# Polarshield_v1_5.net
KiCad netlist of a schematic drawn in EAGLE
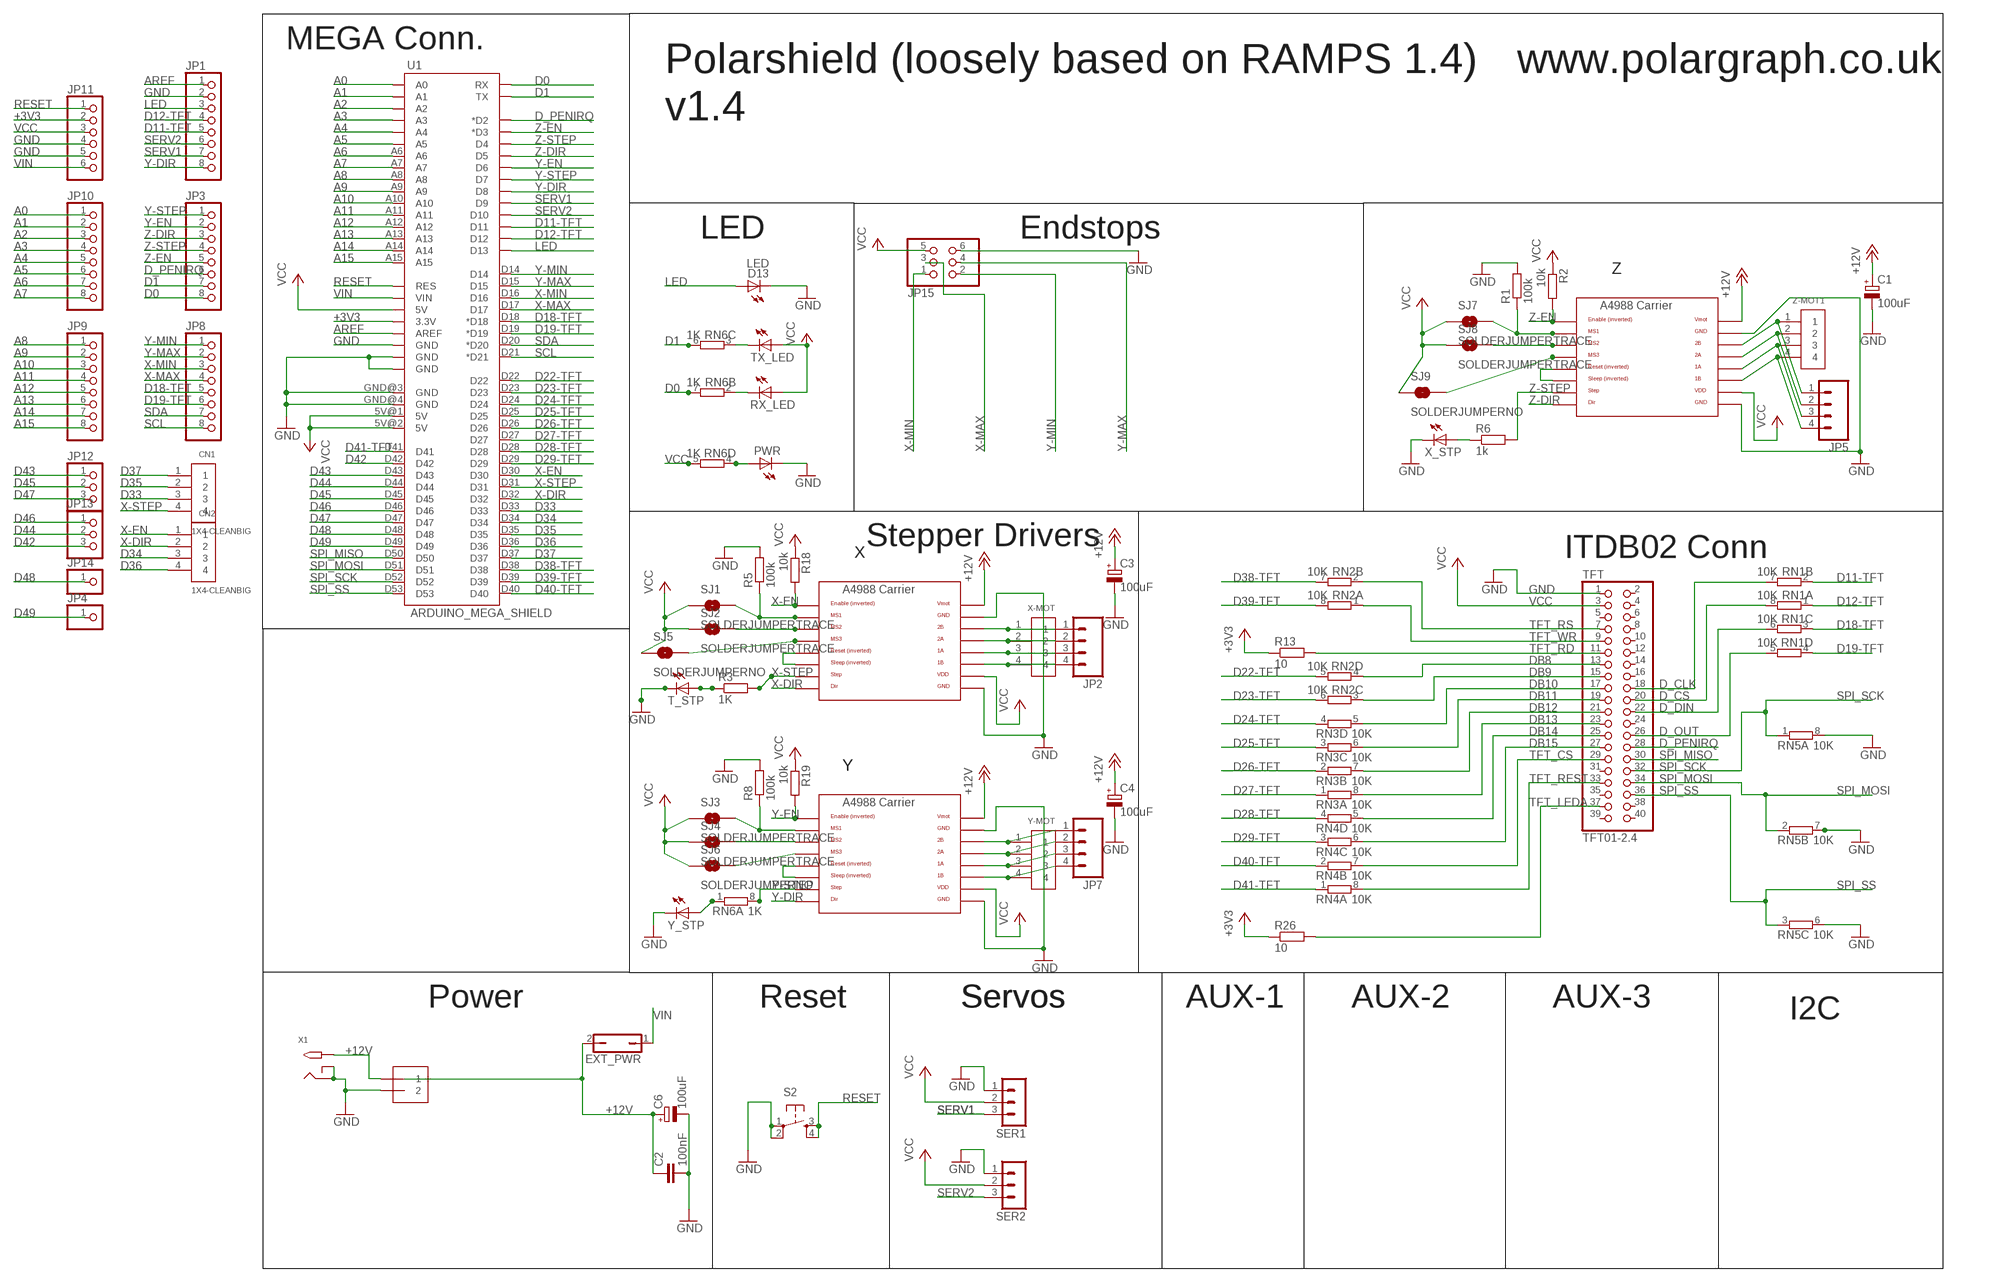
[diagram p0: schematic, sheet 1]

(export (version "E")
  (design (tool "Eeschema 10.0.6"))
  (components
    (comp (ref "C1")
      (value "100uF")
      (footprint "eagle-import:153CLV-0605")
      (libsource (lib "eagle-import") (part "CPOL-EU153CLV-0605"))
    )
    (comp (ref "C2")
      (value "100nF")
      (footprint "eagle-import:C0805")
      (libsource (lib "eagle-import") (part "C-EUC0805"))
    )
    (comp (ref "C3")
      (value "100uF")
      (footprint "eagle-import:153CLV-0605")
      (libsource (lib "eagle-import") (part "CPOL-EU153CLV-0605"))
    )
    (comp (ref "C4")
      (value "100uF")
      (footprint "eagle-import:153CLV-0605")
      (libsource (lib "eagle-import") (part "CPOL-EU153CLV-0605"))
    )
    (comp (ref "C6")
      (value "100uF")
      (footprint "eagle-import:153CLV-0605")
      (libsource (lib "eagle-import") (part "CPOL-EU153CLV-0605"))
    )
    (comp (ref "CN1")
      (value "1X4-CLEANBIG")
      (footprint "eagle-import:1X04-CLEANBIG")
      (libsource (lib "eagle-import") (part "1X4-CLEANBIG"))
    )
    (comp (ref "CN2")
      (value "1X4-CLEANBIG")
      (footprint "eagle-import:1X04-CLEANBIG")
      (libsource (lib "eagle-import") (part "1X4-CLEANBIG"))
    )
    (comp (ref "D13")
      (value "LED")
      (footprint "eagle-import:CHIP-LED0805")
      (libsource (lib "eagle-import") (part "LEDCHIP-LED0805"))
    )
    (comp (ref "EXT_PWR")
      (value "JP1Q")
      (footprint "eagle-import:JP1")
      (libsource (lib "eagle-import") (part "JP1Q"))
    )
    (comp (ref "J1")
      (value "1X2-3.5MM")
      (footprint "eagle-import:1X2-3.5MM")
      (libsource (lib "eagle-import") (part "1X2-3.5MM"))
    )
    (comp (ref "JP1")
      (value "PINHD-1X8CLEANBIG")
      (footprint "eagle-import:1X08-CLEANBIG")
      (libsource (lib "eagle-import") (part "PINHD-1X8CLEANBIG"))
    )
    (comp (ref "JP2")
      (value "M04SCREW")
      (footprint "eagle-import:SCREWTERMINAL-3.5MM-4")
      (libsource (lib "eagle-import") (part "M04SCREW"))
    )
    (comp (ref "JP3")
      (value "PINHD-1X8CLEANBIG")
      (footprint "eagle-import:1X08-CLEANBIG")
      (libsource (lib "eagle-import") (part "PINHD-1X8CLEANBIG"))
    )
    (comp (ref "JP4")
      (value "PINHD-1X1CB")
      (footprint "eagle-import:1X01-CLEANBIG")
      (libsource (lib "eagle-import") (part "PINHD-1X1CB"))
    )
    (comp (ref "JP5")
      (value "M04SCREW")
      (footprint "eagle-import:SCREWTERMINAL-3.5MM-4")
      (libsource (lib "eagle-import") (part "M04SCREW"))
    )
    (comp (ref "JP7")
      (value "M04SCREW")
      (footprint "eagle-import:SCREWTERMINAL-3.5MM-4")
      (libsource (lib "eagle-import") (part "M04SCREW"))
    )
    (comp (ref "JP8")
      (value "PINHD-1X8CLEANBIG")
      (footprint "eagle-import:1X08-CLEANBIG")
      (libsource (lib "eagle-import") (part "PINHD-1X8CLEANBIG"))
    )
    (comp (ref "JP9")
      (value "PINHD-1X8CLEANBIG")
      (footprint "eagle-import:1X08-CLEANBIG")
      (libsource (lib "eagle-import") (part "PINHD-1X8CLEANBIG"))
    )
    (comp (ref "JP10")
      (value "PINHD-1X8CLEANBIG")
      (footprint "eagle-import:1X08-CLEANBIG")
      (libsource (lib "eagle-import") (part "PINHD-1X8CLEANBIG"))
    )
    (comp (ref "JP11")
      (value "PINHD-1X6CB")
      (footprint "eagle-import:1X06-CLEANBIG")
      (libsource (lib "eagle-import") (part "PINHD-1X6CB"))
    )
    (comp (ref "JP12")
      (value "PINHD-1X3CB")
      (footprint "eagle-import:1X03-CLEANBIG")
      (libsource (lib "eagle-import") (part "PINHD-1X3CB"))
    )
    (comp (ref "JP13")
      (value "PINHD-1X3CB")
      (footprint "eagle-import:1X03-CLEANBIG")
      (libsource (lib "eagle-import") (part "PINHD-1X3CB"))
    )
    (comp (ref "JP14")
      (value "PINHD-1X1CB")
      (footprint "eagle-import:1X01-CLEANBIG")
      (libsource (lib "eagle-import") (part "PINHD-1X1CB"))
    )
    (comp (ref "JP15")
      (value "PINHD-2X3")
      (footprint "eagle-import:2X03")
      (libsource (lib "eagle-import") (part "PINHD-2X3"))
    )
    (comp (ref "PWR")
      (value "LEDCHIP-LED0805")
      (footprint "eagle-import:CHIP-LED0805")
      (libsource (lib "eagle-import") (part "LEDCHIP-LED0805"))
    )
    (comp (ref "R1")
      (value "100k")
      (footprint "eagle-import:R0805")
      (libsource (lib "eagle-import") (part "R-EU_R0805"))
    )
    (comp (ref "R2")
      (value "10k")
      (footprint "eagle-import:R0805")
      (libsource (lib "eagle-import") (part "R-EU_R0805"))
    )
    (comp (ref "R3")
      (value "1K")
      (footprint "eagle-import:R0805")
      (libsource (lib "eagle-import") (part "R-EU_R0805"))
    )
    (comp (ref "R5")
      (value "100k")
      (footprint "eagle-import:R0805")
      (libsource (lib "eagle-import") (part "R-EU_R0805"))
    )
    (comp (ref "R6")
      (value "1k")
      (footprint "eagle-import:R0805")
      (libsource (lib "eagle-import") (part "R-EU_R0805"))
    )
    (comp (ref "R8")
      (value "100k")
      (footprint "eagle-import:R0805")
      (libsource (lib "eagle-import") (part "R-EU_R0805"))
    )
    (comp (ref "R13")
      (value "10")
      (footprint "eagle-import:R0805")
      (libsource (lib "eagle-import") (part "resistor_R-EU_R0805"))
    )
    (comp (ref "R18")
      (value "10k")
      (footprint "eagle-import:R0805")
      (libsource (lib "eagle-import") (part "R-EU_R0805"))
    )
    (comp (ref "R19")
      (value "10k")
      (footprint "eagle-import:R0805")
      (libsource (lib "eagle-import") (part "R-EU_R0805"))
    )
    (comp (ref "R26")
      (value "10")
      (footprint "eagle-import:R0805")
      (libsource (lib "eagle-import") (part "resistor_R-EU_R0805"))
    )
    (comp (ref "RN1")
      (value "10K")
      (footprint "eagle-import:EXBS8V")
      (libsource (lib "eagle-import") (part "4R-NEXBS8V"))
    )
    (comp (ref "RN2")
      (value "10K")
      (footprint "eagle-import:EXBS8V")
      (libsource (lib "eagle-import") (part "4R-NEXBS8V"))
    )
    (comp (ref "RN3")
      (value "10K")
      (footprint "eagle-import:EXBS8V")
      (libsource (lib "eagle-import") (part "4R-NEXBS8V"))
    )
    (comp (ref "RN4")
      (value "10K")
      (footprint "eagle-import:EXBS8V")
      (libsource (lib "eagle-import") (part "4R-NEXBS8V"))
    )
    (comp (ref "RN5")
      (value "10K")
      (footprint "eagle-import:EXBS8V")
      (libsource (lib "eagle-import") (part "4R-NEXBS8V"))
    )
    (comp (ref "RN6")
      (value "1K")
      (footprint "eagle-import:EXBS8V")
      (libsource (lib "eagle-import") (part "4R-NEXBS8V"))
    )
    (comp (ref "RX_LED")
      (value "LEDCHIP-LED0805")
      (footprint "eagle-import:CHIP-LED0805")
      (libsource (lib "eagle-import") (part "LEDCHIP-LED0805"))
    )
    (comp (ref "S2")
      (value "TAC_SWITCHPTH")
      (footprint "eagle-import:TACTILE-PTH")
      (libsource (lib "eagle-import") (part "TAC_SWITCHPTH"))
    )
    (comp (ref "SER1")
      (value "3PIN-HEADER")
      (footprint "eagle-import:3PIN-HEADER")
      (libsource (lib "eagle-import") (part "3PIN-HEADER"))
    )
    (comp (ref "SER2")
      (value "3PIN-HEADER")
      (footprint "eagle-import:3PIN-HEADER")
      (libsource (lib "eagle-import") (part "3PIN-HEADER"))
    )
    (comp (ref "SJ1")
      (value "SOLDERJUMPERTRACE")
      (footprint "eagle-import:SJ_2S-TRACE")
      (libsource (lib "eagle-import") (part "SOLDERJUMPERTRACE"))
    )
    (comp (ref "SJ2")
      (value "SOLDERJUMPERTRACE")
      (footprint "eagle-import:SJ_2S-TRACE")
      (libsource (lib "eagle-import") (part "SOLDERJUMPERTRACE"))
    )
    (comp (ref "SJ3")
      (value "SOLDERJUMPERTRACE")
      (footprint "eagle-import:SJ_2S-TRACE")
      (libsource (lib "eagle-import") (part "SOLDERJUMPERTRACE"))
    )
    (comp (ref "SJ4")
      (value "SOLDERJUMPERTRACE")
      (footprint "eagle-import:SJ_2S-TRACE")
      (libsource (lib "eagle-import") (part "SOLDERJUMPERTRACE"))
    )
    (comp (ref "SJ5")
      (value "SOLDERJUMPERNO")
      (footprint "eagle-import:SJ_2S-NO")
      (libsource (lib "eagle-import") (part "SOLDERJUMPERNO"))
    )
    (comp (ref "SJ6")
      (value "SOLDERJUMPERNO")
      (footprint "eagle-import:SJ_2S-NO")
      (libsource (lib "eagle-import") (part "SOLDERJUMPERNO"))
    )
    (comp (ref "SJ7")
      (value "SOLDERJUMPERTRACE")
      (footprint "eagle-import:SJ_2S-TRACE")
      (libsource (lib "eagle-import") (part "SOLDERJUMPERTRACE"))
    )
    (comp (ref "SJ8")
      (value "SOLDERJUMPERTRACE")
      (footprint "eagle-import:SJ_2S-TRACE")
      (libsource (lib "eagle-import") (part "SOLDERJUMPERTRACE"))
    )
    (comp (ref "SJ9")
      (value "SOLDERJUMPERNO")
      (footprint "eagle-import:SJ_2S-NO")
      (libsource (lib "eagle-import") (part "SOLDERJUMPERNO"))
    )
    (comp (ref "TFT")
      (value "TFT01-2.4")
      (footprint "eagle-import:TFT01-2.4")
      (libsource (lib "eagle-import") (part "TFT01-2.4"))
    )
    (comp (ref "TX_LED")
      (value "LEDCHIP-LED0805")
      (footprint "eagle-import:CHIP-LED0805")
      (libsource (lib "eagle-import") (part "LEDCHIP-LED0805"))
    )
    (comp (ref "T_STP")
      (value "LEDCHIP-LED0805")
      (footprint "eagle-import:CHIP-LED0805")
      (libsource (lib "eagle-import") (part "LEDCHIP-LED0805"))
    )
    (comp (ref "U$1")
      (value "A4988BREAKOUT")
      (footprint "eagle-import:A4988BREAKOUT")
      (libsource (lib "eagle-import") (part "A4988BREAKOUT"))
    )
    (comp (ref "U$6")
      (value "A4988BREAKOUT")
      (footprint "eagle-import:A4988BREAKOUT")
      (libsource (lib "eagle-import") (part "A4988BREAKOUT"))
    )
    (comp (ref "U$7")
      (value "A4988BREAKOUT")
      (footprint "eagle-import:A4988BREAKOUT")
      (libsource (lib "eagle-import") (part "A4988BREAKOUT"))
    )
    (comp (ref "U1")
      (value "ARDUINO_MEGA_SHIELD")
      (footprint "eagle-import:ARDUINO_MEGA_SHIELD")
      (libsource (lib "eagle-import") (part "ARDUINO_MEGA_SHIELD"))
    )
    (comp (ref "X-MOT")
      (value "1X4-BIG")
      (footprint "eagle-import:1X04-BIG")
      (libsource (lib "eagle-import") (part "1X4-BIG"))
    )
    (comp (ref "X1")
      (value "2.1MMJACKTHM")
      (footprint "eagle-import:PJ-102A")
      (libsource (lib "eagle-import") (part "2.1MMJACKTHM"))
    )
    (comp (ref "X_STP")
      (value "LEDCHIP-LED0805")
      (footprint "eagle-import:CHIP-LED0805")
      (libsource (lib "eagle-import") (part "LEDCHIP-LED0805"))
    )
    (comp (ref "Y-MOT")
      (value "1X4-BIG")
      (footprint "eagle-import:1X04-BIG")
      (libsource (lib "eagle-import") (part "1X4-BIG"))
    )
    (comp (ref "Y_STP")
      (value "LEDCHIP-LED0805")
      (footprint "eagle-import:CHIP-LED0805")
      (libsource (lib "eagle-import") (part "LEDCHIP-LED0805"))
    )
    (comp (ref "Z-MOT1")
      (value "1X4-BIG")
      (footprint "eagle-import:1X04-BIG")
      (libsource (lib "eagle-import") (part "1X4-BIG"))
    )
  )
  (nets
    (net (code "1") (name "+3V3") (class "Default")
      (node (ref "JP11") (pin "2") (pinfunction "2_2") (pintype "passive"))
      (node (ref "R13") (pin "1") (pinfunction "1_1") (pintype "passive"))
      (node (ref "R26") (pin "1") (pinfunction "1_1") (pintype "passive"))
      (node (ref "U1") (pin "3.3V") (pinfunction "3.3V_3.3V") (pintype "bidirectional"))
    )
    (net (code "2") (name "+12V") (class "Default")
      (node (ref "C1") (pin "+") (pinfunction "+_+") (pintype "passive"))
      (node (ref "C2") (pin "1") (pinfunction "1_1") (pintype "passive"))
      (node (ref "C3") (pin "+") (pinfunction "+_+") (pintype "passive"))
      (node (ref "C4") (pin "+") (pinfunction "+_+") (pintype "passive"))
      (node (ref "C6") (pin "+") (pinfunction "+_+") (pintype "passive"))
      (node (ref "EXT_PWR") (pin "2") (pinfunction "2_2") (pintype "passive"))
      (node (ref "J1") (pin "1") (pinfunction "1_1") (pintype "passive"))
      (node (ref "U$1") (pin "VMOT") (pinfunction "VMOT_VMOT") (pintype "power_in"))
      (node (ref "U$6") (pin "VMOT") (pinfunction "VMOT_VMOT") (pintype "power_in"))
      (node (ref "U$7") (pin "VMOT") (pinfunction "VMOT_VMOT") (pintype "power_in"))
      (node (ref "X1") (pin "TIP") (pinfunction "TIP_TIP") (pintype "bidirectional"))
    )
    (net (code "3") (name "/A0") (class "Default")
      (node (ref "JP10") (pin "1") (pinfunction "1_1") (pintype "passive"))
      (node (ref "U1") (pin "A0") (pinfunction "A0_A0") (pintype "bidirectional"))
    )
    (net (code "4") (name "/A1") (class "Default")
      (node (ref "JP10") (pin "2") (pinfunction "2_2") (pintype "passive"))
      (node (ref "U1") (pin "A1") (pinfunction "A1_A1") (pintype "bidirectional"))
    )
    (net (code "5") (name "/A2") (class "Default")
      (node (ref "JP10") (pin "3") (pinfunction "3_3") (pintype "passive"))
      (node (ref "U1") (pin "A2") (pinfunction "A2_A2") (pintype "bidirectional"))
    )
    (net (code "6") (name "/A3") (class "Default")
      (node (ref "JP10") (pin "4") (pinfunction "4_4") (pintype "passive"))
      (node (ref "U1") (pin "A3") (pinfunction "A3_A3") (pintype "bidirectional"))
    )
    (net (code "7") (name "/A4") (class "Default")
      (node (ref "JP10") (pin "5") (pinfunction "5_5") (pintype "passive"))
      (node (ref "U1") (pin "A4") (pinfunction "A4_A4") (pintype "bidirectional"))
    )
    (net (code "8") (name "/A5") (class "Default")
      (node (ref "JP10") (pin "6") (pinfunction "6_6") (pintype "passive"))
      (node (ref "U1") (pin "A5") (pinfunction "A5_A5") (pintype "bidirectional"))
    )
    (net (code "9") (name "/A6") (class "Default")
      (node (ref "JP10") (pin "7") (pinfunction "7_7") (pintype "passive"))
      (node (ref "U1") (pin "A6") (pinfunction "A6_A6") (pintype "bidirectional"))
    )
    (net (code "10") (name "/A7") (class "Default")
      (node (ref "JP10") (pin "8") (pinfunction "8_8") (pintype "passive"))
      (node (ref "U1") (pin "A7") (pinfunction "A7_A7") (pintype "bidirectional"))
    )
    (net (code "11") (name "/A8") (class "Default")
      (node (ref "JP9") (pin "1") (pinfunction "1_1") (pintype "passive"))
      (node (ref "U1") (pin "A8") (pinfunction "A8_A8") (pintype "bidirectional"))
    )
    (net (code "12") (name "/A9") (class "Default")
      (node (ref "JP9") (pin "2") (pinfunction "2_2") (pintype "passive"))
      (node (ref "U1") (pin "A9") (pinfunction "A9_A9") (pintype "bidirectional"))
    )
    (net (code "13") (name "/A10") (class "Default")
      (node (ref "JP9") (pin "3") (pinfunction "3_3") (pintype "passive"))
      (node (ref "U1") (pin "A10") (pinfunction "A10_A10") (pintype "bidirectional"))
    )
    (net (code "14") (name "/A11") (class "Default")
      (node (ref "JP9") (pin "4") (pinfunction "4_4") (pintype "passive"))
      (node (ref "U1") (pin "A11") (pinfunction "A11_A11") (pintype "bidirectional"))
    )
    (net (code "15") (name "/A12") (class "Default")
      (node (ref "JP9") (pin "5") (pinfunction "5_5") (pintype "passive"))
      (node (ref "U1") (pin "A12") (pinfunction "A12_A12") (pintype "bidirectional"))
    )
    (net (code "16") (name "/A13") (class "Default")
      (node (ref "JP9") (pin "6") (pinfunction "6_6") (pintype "passive"))
      (node (ref "U1") (pin "A13") (pinfunction "A13_A13") (pintype "bidirectional"))
    )
    (net (code "17") (name "/A14") (class "Default")
      (node (ref "JP9") (pin "7") (pinfunction "7_7") (pintype "passive"))
      (node (ref "U1") (pin "A14") (pinfunction "A14_A14") (pintype "bidirectional"))
    )
    (net (code "18") (name "/A15") (class "Default")
      (node (ref "JP9") (pin "8") (pinfunction "8_8") (pintype "passive"))
      (node (ref "U1") (pin "A15") (pinfunction "A15_A15") (pintype "bidirectional"))
    )
    (net (code "19") (name "/AREF") (class "Default")
      (node (ref "JP1") (pin "1") (pinfunction "1_1") (pintype "passive"))
      (node (ref "U1") (pin "AREF") (pinfunction "AREF_AREF") (pintype "bidirectional"))
    )
    (net (code "20") (name "/D0") (class "Default")
      (node (ref "JP3") (pin "8") (pinfunction "8_8") (pintype "passive"))
      (node (ref "RN6") (pin "7") (pinfunction "2_7") (pintype "passive"))
      (node (ref "U1") (pin "RX") (pinfunction "RX_RX") (pintype "bidirectional"))
    )
    (net (code "21") (name "/D1") (class "Default")
      (node (ref "JP3") (pin "7") (pinfunction "7_7") (pintype "passive"))
      (node (ref "RN6") (pin "6") (pinfunction "2_6") (pintype "passive"))
      (node (ref "U1") (pin "TX") (pinfunction "TX_TX") (pintype "bidirectional"))
    )
    (net (code "22") (name "/D11-TFT") (class "Default")
      (node (ref "JP1") (pin "5") (pinfunction "5_5") (pintype "passive"))
      (node (ref "RN1") (pin "2") (pinfunction "1_2") (pintype "passive"))
      (node (ref "U1") (pin "D11") (pinfunction "D11_D11") (pintype "bidirectional"))
    )
    (net (code "23") (name "/D12-TFT") (class "Default")
      (node (ref "JP1") (pin "4") (pinfunction "4_4") (pintype "passive"))
      (node (ref "RN1") (pin "1") (pinfunction "1_1") (pintype "passive"))
      (node (ref "U1") (pin "D12") (pinfunction "D12_D12") (pintype "bidirectional"))
    )
    (net (code "24") (name "/D18-TFT") (class "Default")
      (node (ref "JP8") (pin "5") (pinfunction "5_5") (pintype "passive"))
      (node (ref "RN1") (pin "3") (pinfunction "1_3") (pintype "passive"))
      (node (ref "U1") (pin "D18") (pinfunction "*D18_D18") (pintype "bidirectional"))
    )
    (net (code "25") (name "/D19-TFT") (class "Default")
      (node (ref "JP8") (pin "6") (pinfunction "6_6") (pintype "passive"))
      (node (ref "RN1") (pin "4") (pinfunction "1_4") (pintype "passive"))
      (node (ref "U1") (pin "D19") (pinfunction "*D19_D19") (pintype "bidirectional"))
    )
    (net (code "26") (name "/D22-TFT") (class "Default")
      (node (ref "RN2") (pin "5") (pinfunction "2_5") (pintype "passive"))
      (node (ref "U1") (pin "D22") (pinfunction "D22_D22") (pintype "bidirectional"))
    )
    (net (code "27") (name "/D23-TFT") (class "Default")
      (node (ref "RN2") (pin "6") (pinfunction "2_6") (pintype "passive"))
      (node (ref "U1") (pin "D23") (pinfunction "D23_D23") (pintype "bidirectional"))
    )
    (net (code "28") (name "/D24-TFT") (class "Default")
      (node (ref "RN3") (pin "4") (pinfunction "1_4") (pintype "passive"))
      (node (ref "U1") (pin "D24") (pinfunction "D24_D24") (pintype "bidirectional"))
    )
    (net (code "29") (name "/D25-TFT") (class "Default")
      (node (ref "RN3") (pin "3") (pinfunction "1_3") (pintype "passive"))
      (node (ref "U1") (pin "D25") (pinfunction "D25_D25") (pintype "bidirectional"))
    )
    (net (code "30") (name "/D26-TFT") (class "Default")
      (node (ref "RN3") (pin "2") (pinfunction "1_2") (pintype "passive"))
      (node (ref "U1") (pin "D26") (pinfunction "D26_D26") (pintype "bidirectional"))
    )
    (net (code "31") (name "/D27-TFT") (class "Default")
      (node (ref "RN3") (pin "1") (pinfunction "1_1") (pintype "passive"))
      (node (ref "U1") (pin "D27") (pinfunction "D27_D27") (pintype "bidirectional"))
    )
    (net (code "32") (name "/D28-TFT") (class "Default")
      (node (ref "RN4") (pin "4") (pinfunction "1_4") (pintype "passive"))
      (node (ref "U1") (pin "D28") (pinfunction "D28_D28") (pintype "bidirectional"))
    )
    (net (code "33") (name "/D29-TFT") (class "Default")
      (node (ref "RN4") (pin "3") (pinfunction "1_3") (pintype "passive"))
      (node (ref "U1") (pin "D29") (pinfunction "D29_D29") (pintype "bidirectional"))
    )
    (net (code "34") (name "/D33") (class "Default")
      (node (ref "CN1") (pin "3") (pinfunction "3_3") (pintype "bidirectional"))
      (node (ref "U1") (pin "D33") (pinfunction "D33_D33") (pintype "bidirectional"))
    )
    (net (code "35") (name "/D34") (class "Default")
      (node (ref "CN2") (pin "3") (pinfunction "3_3") (pintype "bidirectional"))
      (node (ref "U1") (pin "D34") (pinfunction "D34_D34") (pintype "bidirectional"))
    )
    (net (code "36") (name "/D35") (class "Default")
      (node (ref "CN1") (pin "2") (pinfunction "2_2") (pintype "bidirectional"))
      (node (ref "U1") (pin "D35") (pinfunction "D35_D35") (pintype "bidirectional"))
    )
    (net (code "37") (name "/D36") (class "Default")
      (node (ref "CN2") (pin "4") (pinfunction "4_4") (pintype "bidirectional"))
      (node (ref "U1") (pin "D36") (pinfunction "D36_D36") (pintype "bidirectional"))
    )
    (net (code "38") (name "/D37") (class "Default")
      (node (ref "CN1") (pin "1") (pinfunction "1_1") (pintype "bidirectional"))
      (node (ref "U1") (pin "D37") (pinfunction "D37_D37") (pintype "bidirectional"))
    )
    (net (code "39") (name "/D38-TFT") (class "Default")
      (node (ref "RN2") (pin "7") (pinfunction "2_7") (pintype "passive"))
      (node (ref "U1") (pin "D38") (pinfunction "D38_D38") (pintype "bidirectional"))
    )
    (net (code "40") (name "/D39-TFT") (class "Default")
      (node (ref "RN2") (pin "8") (pinfunction "2_8") (pintype "passive"))
      (node (ref "U1") (pin "D39") (pinfunction "D39_D39") (pintype "bidirectional"))
    )
    (net (code "41") (name "/D40-TFT") (class "Default")
      (node (ref "RN4") (pin "2") (pinfunction "1_2") (pintype "passive"))
      (node (ref "U1") (pin "D40") (pinfunction "D40_D40") (pintype "bidirectional"))
    )
    (net (code "42") (name "/D41-TFT") (class "Default")
      (node (ref "RN4") (pin "1") (pinfunction "1_1") (pintype "passive"))
      (node (ref "U1") (pin "D41") (pinfunction "D41_D41") (pintype "bidirectional"))
    )
    (net (code "43") (name "/D42") (class "Default")
      (node (ref "JP13") (pin "3") (pinfunction "3_3") (pintype "passive"))
      (node (ref "U1") (pin "D42") (pinfunction "D42_D42") (pintype "bidirectional"))
    )
    (net (code "44") (name "/D43") (class "Default")
      (node (ref "JP12") (pin "1") (pinfunction "1_1") (pintype "passive"))
      (node (ref "U1") (pin "D43") (pinfunction "D43_D43") (pintype "bidirectional"))
    )
    (net (code "45") (name "/D44") (class "Default")
      (node (ref "JP13") (pin "2") (pinfunction "2_2") (pintype "passive"))
      (node (ref "U1") (pin "D44") (pinfunction "D44_D44") (pintype "bidirectional"))
    )
    (net (code "46") (name "/D45") (class "Default")
      (node (ref "JP12") (pin "2") (pinfunction "2_2") (pintype "passive"))
      (node (ref "U1") (pin "D45") (pinfunction "D45_D45") (pintype "bidirectional"))
    )
    (net (code "47") (name "/D46") (class "Default")
      (node (ref "JP13") (pin "1") (pinfunction "1_1") (pintype "passive"))
      (node (ref "U1") (pin "D46") (pinfunction "D46_D46") (pintype "bidirectional"))
    )
    (net (code "48") (name "/D47") (class "Default")
      (node (ref "JP12") (pin "3") (pinfunction "3_3") (pintype "passive"))
      (node (ref "U1") (pin "D47") (pinfunction "D47_D47") (pintype "bidirectional"))
    )
    (net (code "49") (name "/D48") (class "Default")
      (node (ref "JP14") (pin "1") (pinfunction "1_1") (pintype "passive"))
      (node (ref "U1") (pin "D48") (pinfunction "D48_D48") (pintype "bidirectional"))
    )
    (net (code "50") (name "/D49") (class "Default")
      (node (ref "JP4") (pin "1") (pinfunction "1_1") (pintype "passive"))
      (node (ref "U1") (pin "D49") (pinfunction "D49_D49") (pintype "bidirectional"))
    )
    (net (code "51") (name "/DB8") (class "Default")
      (node (ref "RN2") (pin "4") (pinfunction "1_4") (pintype "passive"))
      (node (ref "TFT") (pin "13") (pinfunction "13_13") (pintype "passive"))
    )
    (net (code "52") (name "/DB9") (class "Default")
      (node (ref "RN2") (pin "3") (pinfunction "1_3") (pintype "passive"))
      (node (ref "TFT") (pin "15") (pinfunction "15_15") (pintype "passive"))
    )
    (net (code "53") (name "/DB10") (class "Default")
      (node (ref "RN3") (pin "5") (pinfunction "2_5") (pintype "passive"))
      (node (ref "TFT") (pin "17") (pinfunction "17_17") (pintype "passive"))
    )
    (net (code "54") (name "/DB11") (class "Default")
      (node (ref "RN3") (pin "6") (pinfunction "2_6") (pintype "passive"))
      (node (ref "TFT") (pin "19") (pinfunction "19_19") (pintype "passive"))
    )
    (net (code "55") (name "/DB12") (class "Default")
      (node (ref "RN3") (pin "7") (pinfunction "2_7") (pintype "passive"))
      (node (ref "TFT") (pin "21") (pinfunction "21_21") (pintype "passive"))
    )
    (net (code "56") (name "/DB13") (class "Default")
      (node (ref "RN3") (pin "8") (pinfunction "2_8") (pintype "passive"))
      (node (ref "TFT") (pin "23") (pinfunction "23_23") (pintype "passive"))
    )
    (net (code "57") (name "/DB14") (class "Default")
      (node (ref "RN4") (pin "5") (pinfunction "2_5") (pintype "passive"))
      (node (ref "TFT") (pin "25") (pinfunction "25_25") (pintype "passive"))
    )
    (net (code "58") (name "/DB15") (class "Default")
      (node (ref "RN4") (pin "6") (pinfunction "2_6") (pintype "passive"))
      (node (ref "TFT") (pin "27") (pinfunction "27_27") (pintype "passive"))
    )
    (net (code "59") (name "/D_CLK") (class "Default")
      (node (ref "RN1") (pin "7") (pinfunction "2_7") (pintype "passive"))
      (node (ref "TFT") (pin "18") (pinfunction "18_18") (pintype "passive"))
    )
    (net (code "60") (name "/D_CS") (class "Default")
      (node (ref "RN1") (pin "8") (pinfunction "2_8") (pintype "passive"))
      (node (ref "TFT") (pin "20") (pinfunction "20_20") (pintype "passive"))
    )
    (net (code "61") (name "/D_DIN") (class "Default")
      (node (ref "RN1") (pin "6") (pinfunction "2_6") (pintype "passive"))
      (node (ref "TFT") (pin "22") (pinfunction "22_22") (pintype "passive"))
    )
    (net (code "62") (name "/D_OUT") (class "Default")
      (node (ref "RN1") (pin "5") (pinfunction "2_5") (pintype "passive"))
      (node (ref "TFT") (pin "26") (pinfunction "26_26") (pintype "passive"))
    )
    (net (code "63") (name "/D_PENIRQ") (class "Default")
      (node (ref "JP3") (pin "6") (pinfunction "6_6") (pintype "passive"))
      (node (ref "TFT") (pin "28") (pinfunction "28_28") (pintype "passive"))
      (node (ref "U1") (pin "D2") (pinfunction "*D2_D2") (pintype "bidirectional"))
    )
    (net (code "64") (name "/LED") (class "Default")
      (node (ref "D13") (pin "A") (pinfunction "A_A") (pintype "passive"))
      (node (ref "JP1") (pin "3") (pinfunction "3_3") (pintype "passive"))
      (node (ref "U1") (pin "D13") (pinfunction "D13_D13") (pintype "bidirectional"))
    )
    (net (code "65") (name "/RESET") (class "Default")
      (node (ref "JP11") (pin "1") (pinfunction "1_1") (pintype "passive"))
      (node (ref "S2") (pin "3") (pinfunction "3_3") (pintype "passive"))
      (node (ref "S2") (pin "4") (pinfunction "4_4") (pintype "passive"))
      (node (ref "U1") (pin "RES") (pinfunction "RES_RES") (pintype "bidirectional"))
    )
    (net (code "66") (name "/SCL") (class "Default")
      (node (ref "JP8") (pin "8") (pinfunction "8_8") (pintype "passive"))
      (node (ref "U1") (pin "D21") (pinfunction "*D21_D21") (pintype "bidirectional"))
    )
    (net (code "67") (name "/SDA") (class "Default")
      (node (ref "JP8") (pin "7") (pinfunction "7_7") (pintype "passive"))
      (node (ref "U1") (pin "D20") (pinfunction "*D20_D20") (pintype "bidirectional"))
    )
    (net (code "68") (name "/SERV1") (class "Default")
      (node (ref "JP1") (pin "7") (pinfunction "7_7") (pintype "passive"))
      (node (ref "SER1") (pin "3") (pinfunction "3_3") (pintype "passive"))
      (node (ref "U1") (pin "D9") (pinfunction "D9_D9") (pintype "bidirectional"))
    )
    (net (code "69") (name "/SERV2") (class "Default")
      (node (ref "JP1") (pin "6") (pinfunction "6_6") (pintype "passive"))
      (node (ref "SER2") (pin "3") (pinfunction "3_3") (pintype "passive"))
      (node (ref "U1") (pin "D10") (pinfunction "D10_D10") (pintype "bidirectional"))
    )
    (net (code "70") (name "/SPI_MISO") (class "Default")
      (node (ref "TFT") (pin "30") (pinfunction "30_30") (pintype "passive"))
      (node (ref "U1") (pin "D50") (pinfunction "D50_D50") (pintype "bidirectional"))
    )
    (net (code "71") (name "/SPI_MOSI") (class "Default")
      (node (ref "RN5") (pin "2") (pinfunction "1_2") (pintype "passive"))
      (node (ref "TFT") (pin "34") (pinfunction "34_34") (pintype "passive"))
      (node (ref "U1") (pin "D51") (pinfunction "D51_D51") (pintype "bidirectional"))
    )
    (net (code "72") (name "/SPI_SCK") (class "Default")
      (node (ref "RN5") (pin "1") (pinfunction "1_1") (pintype "passive"))
      (node (ref "TFT") (pin "32") (pinfunction "32_32") (pintype "passive"))
      (node (ref "U1") (pin "D52") (pinfunction "D52_D52") (pintype "bidirectional"))
    )
    (net (code "73") (name "/SPI_SS") (class "Default")
      (node (ref "RN5") (pin "3") (pinfunction "1_3") (pintype "passive"))
      (node (ref "TFT") (pin "36") (pinfunction "36_36") (pintype "passive"))
      (node (ref "U1") (pin "D53") (pinfunction "D53_D53") (pintype "bidirectional"))
    )
    (net (code "74") (name "/TFT_CS") (class "Default")
      (node (ref "RN4") (pin "7") (pinfunction "2_7") (pintype "passive"))
      (node (ref "TFT") (pin "29") (pinfunction "29_29") (pintype "passive"))
    )
    (net (code "75") (name "/TFT_LEDA") (class "Default")
      (node (ref "R26") (pin "2") (pinfunction "2_2") (pintype "passive"))
      (node (ref "TFT") (pin "37") (pinfunction "37_37") (pintype "passive"))
    )
    (net (code "76") (name "/TFT_RD") (class "Default")
      (node (ref "R13") (pin "2") (pinfunction "2_2") (pintype "passive"))
      (node (ref "TFT") (pin "11") (pinfunction "11_11") (pintype "passive"))
    )
    (net (code "77") (name "/TFT_REST") (class "Default")
      (node (ref "RN4") (pin "8") (pinfunction "2_8") (pintype "passive"))
      (node (ref "TFT") (pin "33") (pinfunction "33_33") (pintype "passive"))
    )
    (net (code "78") (name "/TFT_RS") (class "Default")
      (node (ref "RN2") (pin "2") (pinfunction "1_2") (pintype "passive"))
      (node (ref "TFT") (pin "7") (pinfunction "7_7") (pintype "passive"))
    )
    (net (code "79") (name "/TFT_WR") (class "Default")
      (node (ref "RN2") (pin "1") (pinfunction "1_1") (pintype "passive"))
      (node (ref "TFT") (pin "9") (pinfunction "9_9") (pintype "passive"))
    )
    (net (code "80") (name "/VIN") (class "Default")
      (node (ref "EXT_PWR") (pin "1") (pinfunction "1_1") (pintype "passive"))
      (node (ref "JP11") (pin "6") (pinfunction "6_6") (pintype "passive"))
      (node (ref "U1") (pin "VIN") (pinfunction "VIN_VIN") (pintype "bidirectional"))
    )
    (net (code "81") (name "/X-DIR") (class "Default")
      (node (ref "CN2") (pin "2") (pinfunction "2_2") (pintype "bidirectional"))
      (node (ref "U$6") (pin "DIR") (pinfunction "DIR_DIR") (pintype "input"))
      (node (ref "U1") (pin "D32") (pinfunction "D32_D32") (pintype "bidirectional"))
    )
    (net (code "82") (name "/X-EN") (class "Default")
      (node (ref "CN2") (pin "1") (pinfunction "1_1") (pintype "bidirectional"))
      (node (ref "R18") (pin "2") (pinfunction "2_2") (pintype "passive"))
      (node (ref "U$6") (pin "EN") (pinfunction "EN_EN") (pintype "input"))
      (node (ref "U1") (pin "D30") (pinfunction "D30_D30") (pintype "bidirectional"))
    )
    (net (code "83") (name "/X-MAX") (class "Default")
      (node (ref "JP15") (pin "3") (pinfunction "3_3") (pintype "passive"))
      (node (ref "JP8") (pin "4") (pinfunction "4_4") (pintype "passive"))
      (node (ref "U1") (pin "D17") (pinfunction "D17_D17") (pintype "bidirectional"))
    )
    (net (code "84") (name "/X-MIN") (class "Default")
      (node (ref "JP15") (pin "1") (pinfunction "1_1") (pintype "passive"))
      (node (ref "JP8") (pin "3") (pinfunction "3_3") (pintype "passive"))
      (node (ref "U1") (pin "D16") (pinfunction "D16_D16") (pintype "bidirectional"))
    )
    (net (code "85") (name "/X-STEP") (class "Default")
      (node (ref "CN1") (pin "4") (pinfunction "4_4") (pintype "bidirectional"))
      (node (ref "R3") (pin "2") (pinfunction "2_2") (pintype "passive"))
      (node (ref "U$6") (pin "STEP") (pinfunction "STEP_STEP") (pintype "input"))
      (node (ref "U1") (pin "D31") (pinfunction "D31_D31") (pintype "bidirectional"))
    )
    (net (code "86") (name "/Y-DIR") (class "Default")
      (node (ref "JP1") (pin "8") (pinfunction "8_8") (pintype "passive"))
      (node (ref "U$7") (pin "DIR") (pinfunction "DIR_DIR") (pintype "input"))
      (node (ref "U1") (pin "D8") (pinfunction "D8_D8") (pintype "bidirectional"))
    )
    (net (code "87") (name "/Y-EN") (class "Default")
      (node (ref "JP3") (pin "2") (pinfunction "2_2") (pintype "passive"))
      (node (ref "R19") (pin "2") (pinfunction "2_2") (pintype "passive"))
      (node (ref "U$7") (pin "EN") (pinfunction "EN_EN") (pintype "input"))
      (node (ref "U1") (pin "D6") (pinfunction "D6_D6") (pintype "bidirectional"))
    )
    (net (code "88") (name "/Y-MAX") (class "Default")
      (node (ref "JP15") (pin "4") (pinfunction "4_4") (pintype "passive"))
      (node (ref "JP8") (pin "2") (pinfunction "2_2") (pintype "passive"))
      (node (ref "U1") (pin "D15") (pinfunction "D15_D15") (pintype "bidirectional"))
    )
    (net (code "89") (name "/Y-MIN") (class "Default")
      (node (ref "JP15") (pin "2") (pinfunction "2_2") (pintype "passive"))
      (node (ref "JP8") (pin "1") (pinfunction "1_1") (pintype "passive"))
      (node (ref "U1") (pin "D14") (pinfunction "D14_D14") (pintype "bidirectional"))
    )
    (net (code "90") (name "/Y-STEP") (class "Default")
      (node (ref "JP3") (pin "1") (pinfunction "1_1") (pintype "passive"))
      (node (ref "RN6") (pin "8") (pinfunction "2_8") (pintype "passive"))
      (node (ref "U$7") (pin "STEP") (pinfunction "STEP_STEP") (pintype "input"))
      (node (ref "U1") (pin "D7") (pinfunction "D7_D7") (pintype "bidirectional"))
    )
    (net (code "91") (name "/Z-DIR") (class "Default")
      (node (ref "JP3") (pin "3") (pinfunction "3_3") (pintype "passive"))
      (node (ref "U$1") (pin "DIR") (pinfunction "DIR_DIR") (pintype "input"))
      (node (ref "U1") (pin "D5") (pinfunction "D5_D5") (pintype "bidirectional"))
    )
    (net (code "92") (name "/Z-EN") (class "Default")
      (node (ref "JP3") (pin "5") (pinfunction "5_5") (pintype "passive"))
      (node (ref "R2") (pin "2") (pinfunction "2_2") (pintype "passive"))
      (node (ref "U$1") (pin "EN") (pinfunction "EN_EN") (pintype "input"))
      (node (ref "U1") (pin "D3") (pinfunction "*D3_D3") (pintype "bidirectional"))
    )
    (net (code "93") (name "/Z-STEP") (class "Default")
      (node (ref "JP3") (pin "4") (pinfunction "4_4") (pintype "passive"))
      (node (ref "R6") (pin "2") (pinfunction "2_2") (pintype "passive"))
      (node (ref "U$1") (pin "STEP") (pinfunction "STEP_STEP") (pintype "input"))
      (node (ref "U1") (pin "D4") (pinfunction "D4_D4") (pintype "bidirectional"))
    )
    (net (code "94") (name "GND") (class "Default")
      (node (ref "C1") (pin "-") (pinfunction "-_-") (pintype "passive"))
      (node (ref "C2") (pin "2") (pinfunction "2_2") (pintype "passive"))
      (node (ref "C3") (pin "-") (pinfunction "-_-") (pintype "passive"))
      (node (ref "C4") (pin "-") (pinfunction "-_-") (pintype "passive"))
      (node (ref "C6") (pin "-") (pinfunction "-_-") (pintype "passive"))
      (node (ref "D13") (pin "C") (pinfunction "C_C") (pintype "passive"))
      (node (ref "J1") (pin "2") (pinfunction "2_2") (pintype "passive"))
      (node (ref "JP1") (pin "2") (pinfunction "2_2") (pintype "passive"))
      (node (ref "JP11") (pin "4") (pinfunction "4_4") (pintype "passive"))
      (node (ref "JP11") (pin "5") (pinfunction "5_5") (pintype "passive"))
      (node (ref "JP15") (pin "6") (pinfunction "6_6") (pintype "passive"))
      (node (ref "PWR") (pin "C") (pinfunction "C_C") (pintype "passive"))
      (node (ref "R1") (pin "2") (pinfunction "2_2") (pintype "passive"))
      (node (ref "R5") (pin "2") (pinfunction "2_2") (pintype "passive"))
      (node (ref "R8") (pin "2") (pinfunction "2_2") (pintype "passive"))
      (node (ref "RN5") (pin "6") (pinfunction "2_6") (pintype "passive"))
      (node (ref "RN5") (pin "7") (pinfunction "2_7") (pintype "passive"))
      (node (ref "RN5") (pin "8") (pinfunction "2_8") (pintype "passive"))
      (node (ref "S2") (pin "1") (pinfunction "1_1") (pintype "passive"))
      (node (ref "S2") (pin "2") (pinfunction "2_2") (pintype "passive"))
      (node (ref "SER1") (pin "1") (pinfunction "1_1") (pintype "passive"))
      (node (ref "SER2") (pin "1") (pinfunction "1_1") (pintype "passive"))
      (node (ref "TFT") (pin "1") (pinfunction "1_1") (pintype "passive"))
      (node (ref "T_STP") (pin "C") (pinfunction "C_C") (pintype "passive"))
      (node (ref "U$1") (pin "GND") (pinfunction "GND_GND") (pintype "power_in"))
      (node (ref "U$1") (pin "GND@0") (pinfunction "GND_GND@0") (pintype "power_in"))
      (node (ref "U$6") (pin "GND") (pinfunction "GND_GND") (pintype "power_in"))
      (node (ref "U$6") (pin "GND@0") (pinfunction "GND_GND@0") (pintype "power_in"))
      (node (ref "U$7") (pin "GND") (pinfunction "GND_GND") (pintype "power_in"))
      (node (ref "U$7") (pin "GND@0") (pinfunction "GND_GND@0") (pintype "power_in"))
      (node (ref "U1") (pin "GND@0") (pinfunction "GND_GND@0") (pintype "power_in"))
      (node (ref "U1") (pin "GND@1") (pinfunction "GND_GND@1") (pintype "power_in"))
      (node (ref "U1") (pin "GND@2") (pinfunction "GND_GND@2") (pintype "power_in"))
      (node (ref "U1") (pin "GND@3") (pinfunction "GND_GND@3") (pintype "power_in"))
      (node (ref "U1") (pin "GND@4") (pinfunction "GND_GND@4") (pintype "power_in"))
      (node (ref "X1") (pin "RING") (pinfunction "RING_RING") (pintype "bidirectional"))
      (node (ref "X1") (pin "RING_SW") (pinfunction "RING_SW_RING_SW") (pintype "bidirectional"))
      (node (ref "X_STP") (pin "C") (pinfunction "C_C") (pintype "passive"))
      (node (ref "Y_STP") (pin "C") (pinfunction "C_C") (pintype "passive"))
    )
    (net (code "95") (name "Net-(JP2-Pad1)") (class "Default")
      (node (ref "JP2") (pin "1") (pinfunction "1_1") (pintype "passive"))
      (node (ref "U$6") (pin "2B") (pinfunction "2B_2B") (pintype "output"))
      (node (ref "X-MOT") (pin "1") (pinfunction "1_1") (pintype "bidirectional"))
    )
    (net (code "96") (name "Net-(JP2-Pad2)") (class "Default")
      (node (ref "JP2") (pin "2") (pinfunction "2_2") (pintype "passive"))
      (node (ref "U$6") (pin "2A") (pinfunction "2A_2A") (pintype "output"))
      (node (ref "X-MOT") (pin "2") (pinfunction "2_2") (pintype "bidirectional"))
    )
    (net (code "97") (name "Net-(JP2-Pad3)") (class "Default")
      (node (ref "JP2") (pin "3") (pinfunction "3_3") (pintype "passive"))
      (node (ref "U$6") (pin "1A") (pinfunction "1A_1A") (pintype "output"))
      (node (ref "X-MOT") (pin "3") (pinfunction "3_3") (pintype "bidirectional"))
    )
    (net (code "98") (name "Net-(JP2-Pad4)") (class "Default")
      (node (ref "JP2") (pin "4") (pinfunction "4_4") (pintype "passive"))
      (node (ref "U$6") (pin "1B") (pinfunction "1B_1B") (pintype "output"))
      (node (ref "X-MOT") (pin "4") (pinfunction "4_4") (pintype "bidirectional"))
    )
    (net (code "99") (name "Net-(JP5-Pad1)") (class "Default")
      (node (ref "JP5") (pin "1") (pinfunction "1_1") (pintype "passive"))
      (node (ref "U$1") (pin "2B") (pinfunction "2B_2B") (pintype "output"))
      (node (ref "Z-MOT1") (pin "1") (pinfunction "1_1") (pintype "bidirectional"))
    )
    (net (code "100") (name "Net-(JP5-Pad2)") (class "Default")
      (node (ref "JP5") (pin "2") (pinfunction "2_2") (pintype "passive"))
      (node (ref "U$1") (pin "2A") (pinfunction "2A_2A") (pintype "output"))
      (node (ref "Z-MOT1") (pin "2") (pinfunction "2_2") (pintype "bidirectional"))
    )
    (net (code "101") (name "Net-(JP5-Pad3)") (class "Default")
      (node (ref "JP5") (pin "3") (pinfunction "3_3") (pintype "passive"))
      (node (ref "U$1") (pin "1A") (pinfunction "1A_1A") (pintype "output"))
      (node (ref "Z-MOT1") (pin "3") (pinfunction "3_3") (pintype "bidirectional"))
    )
    (net (code "102") (name "Net-(JP5-Pad4)") (class "Default")
      (node (ref "JP5") (pin "4") (pinfunction "4_4") (pintype "passive"))
      (node (ref "U$1") (pin "1B") (pinfunction "1B_1B") (pintype "output"))
      (node (ref "Z-MOT1") (pin "4") (pinfunction "4_4") (pintype "bidirectional"))
    )
    (net (code "103") (name "Net-(JP7-Pad1)") (class "Default")
      (node (ref "JP7") (pin "1") (pinfunction "1_1") (pintype "passive"))
      (node (ref "U$7") (pin "2B") (pinfunction "2B_2B") (pintype "output"))
      (node (ref "Y-MOT") (pin "1") (pinfunction "1_1") (pintype "bidirectional"))
    )
    (net (code "104") (name "Net-(JP7-Pad2)") (class "Default")
      (node (ref "JP7") (pin "2") (pinfunction "2_2") (pintype "passive"))
      (node (ref "U$7") (pin "2A") (pinfunction "2A_2A") (pintype "output"))
      (node (ref "Y-MOT") (pin "2") (pinfunction "2_2") (pintype "bidirectional"))
    )
    (net (code "105") (name "Net-(JP7-Pad3)") (class "Default")
      (node (ref "JP7") (pin "3") (pinfunction "3_3") (pintype "passive"))
      (node (ref "U$7") (pin "1A") (pinfunction "1A_1A") (pintype "output"))
      (node (ref "Y-MOT") (pin "3") (pinfunction "3_3") (pintype "bidirectional"))
    )
    (net (code "106") (name "Net-(JP7-Pad4)") (class "Default")
      (node (ref "JP7") (pin "4") (pinfunction "4_4") (pintype "passive"))
      (node (ref "U$7") (pin "1B") (pinfunction "1B_1B") (pintype "output"))
      (node (ref "Y-MOT") (pin "4") (pinfunction "4_4") (pintype "bidirectional"))
    )
    (net (code "107") (name "Net-(R1-Pad1)") (class "Default")
      (node (ref "R1") (pin "1") (pinfunction "1_1") (pintype "passive"))
      (node (ref "SJ7") (pin "2") (pinfunction "2_2") (pintype "passive"))
      (node (ref "U$1") (pin "MS1") (pinfunction "MS1_MS1") (pintype "input"))
    )
    (net (code "108") (name "Net-(R3-Pad1)") (class "Default")
      (node (ref "R3") (pin "1") (pinfunction "1_1") (pintype "passive"))
      (node (ref "T_STP") (pin "A") (pinfunction "A_A") (pintype "passive"))
    )
    (net (code "109") (name "Net-(R5-Pad1)") (class "Default")
      (node (ref "R5") (pin "1") (pinfunction "1_1") (pintype "passive"))
      (node (ref "SJ1") (pin "2") (pinfunction "2_2") (pintype "passive"))
      (node (ref "U$6") (pin "MS1") (pinfunction "MS1_MS1") (pintype "input"))
    )
    (net (code "110") (name "Net-(R6-Pad1)") (class "Default")
      (node (ref "R6") (pin "1") (pinfunction "1_1") (pintype "passive"))
      (node (ref "X_STP") (pin "A") (pinfunction "A_A") (pintype "passive"))
    )
    (net (code "111") (name "Net-(R8-Pad1)") (class "Default")
      (node (ref "R8") (pin "1") (pinfunction "1_1") (pintype "passive"))
      (node (ref "SJ3") (pin "2") (pinfunction "2_2") (pintype "passive"))
      (node (ref "U$7") (pin "MS1") (pinfunction "MS1_MS1") (pintype "input"))
    )
    (net (code "112") (name "Net-(RN6-Pad1)") (class "Default")
      (node (ref "RN6") (pin "1") (pinfunction "1_1") (pintype "passive"))
      (node (ref "Y_STP") (pin "A") (pinfunction "A_A") (pintype "passive"))
    )
    (net (code "113") (name "Net-(RN6B-1)") (class "Default")
      (node (ref "RN6") (pin "2") (pinfunction "1_2") (pintype "passive"))
      (node (ref "RX_LED") (pin "C") (pinfunction "C_C") (pintype "passive"))
    )
    (net (code "114") (name "Net-(RN6C-1)") (class "Default")
      (node (ref "RN6") (pin "3") (pinfunction "1_3") (pintype "passive"))
      (node (ref "TX_LED") (pin "C") (pinfunction "C_C") (pintype "passive"))
    )
    (net (code "115") (name "Net-(RN6D-1)") (class "Default")
      (node (ref "PWR") (pin "A") (pinfunction "A_A") (pintype "passive"))
      (node (ref "RN6") (pin "4") (pinfunction "1_4") (pintype "passive"))
    )
    (net (code "116") (name "Net-(SJ2-Pad2)") (class "Default")
      (node (ref "SJ2") (pin "2") (pinfunction "2_2") (pintype "passive"))
      (node (ref "U$6") (pin "MS2") (pinfunction "MS2_MS2") (pintype "input"))
    )
    (net (code "117") (name "Net-(SJ4-Pad2)") (class "Default")
      (node (ref "SJ4") (pin "2") (pinfunction "2_2") (pintype "passive"))
      (node (ref "U$7") (pin "MS2") (pinfunction "MS2_MS2") (pintype "input"))
    )
    (net (code "118") (name "Net-(SJ5-Pad2)") (class "Default")
      (node (ref "SJ5") (pin "2") (pinfunction "2_2") (pintype "passive"))
      (node (ref "U$6") (pin "MS3") (pinfunction "MS3_MS3") (pintype "input"))
    )
    (net (code "119") (name "Net-(SJ6-Pad2)") (class "Default")
      (node (ref "SJ6") (pin "2") (pinfunction "2_2") (pintype "passive"))
      (node (ref "U$7") (pin "MS3") (pinfunction "MS3_MS3") (pintype "input"))
    )
    (net (code "120") (name "Net-(SJ8-Pad2)") (class "Default")
      (node (ref "SJ8") (pin "2") (pinfunction "2_2") (pintype "passive"))
      (node (ref "U$1") (pin "MS2") (pinfunction "MS2_MS2") (pintype "input"))
    )
    (net (code "121") (name "Net-(SJ9-Pad2)") (class "Default")
      (node (ref "SJ9") (pin "2") (pinfunction "2_2") (pintype "passive"))
      (node (ref "U$1") (pin "MS3") (pinfunction "MS3_MS3") (pintype "input"))
    )
    (net (code "122") (name "Net-(U$1-SLEEP)") (class "Default")
      (node (ref "U$1") (pin "RST") (pinfunction "RST_RST") (pintype "input"))
      (node (ref "U$1") (pin "SLP") (pinfunction "SLEEP_SLP") (pintype "input"))
    )
    (net (code "123") (name "Net-(U$6-SLEEP)") (class "Default")
      (node (ref "U$6") (pin "RST") (pinfunction "RST_RST") (pintype "input"))
      (node (ref "U$6") (pin "SLP") (pinfunction "SLEEP_SLP") (pintype "input"))
    )
    (net (code "124") (name "Net-(U$7-SLEEP)") (class "Default")
      (node (ref "U$7") (pin "RST") (pinfunction "RST_RST") (pintype "input"))
      (node (ref "U$7") (pin "SLP") (pinfunction "SLEEP_SLP") (pintype "input"))
    )
    (net (code "125") (name "VCC") (class "Default")
      (node (ref "JP11") (pin "3") (pinfunction "3_3") (pintype "passive"))
      (node (ref "JP15") (pin "5") (pinfunction "5_5") (pintype "passive"))
      (node (ref "R18") (pin "1") (pinfunction "1_1") (pintype "passive"))
      (node (ref "R19") (pin "1") (pinfunction "1_1") (pintype "passive"))
      (node (ref "R2") (pin "1") (pinfunction "1_1") (pintype "passive"))
      (node (ref "RN6") (pin "5") (pinfunction "2_5") (pintype "passive"))
      (node (ref "RX_LED") (pin "A") (pinfunction "A_A") (pintype "passive"))
      (node (ref "SER1") (pin "2") (pinfunction "2_2") (pintype "passive"))
      (node (ref "SER2") (pin "2") (pinfunction "2_2") (pintype "passive"))
      (node (ref "SJ1") (pin "1") (pinfunction "1_1") (pintype "passive"))
      (node (ref "SJ2") (pin "1") (pinfunction "1_1") (pintype "passive"))
      (node (ref "SJ3") (pin "1") (pinfunction "1_1") (pintype "passive"))
      (node (ref "SJ4") (pin "1") (pinfunction "1_1") (pintype "passive"))
      (node (ref "SJ5") (pin "1") (pinfunction "1_1") (pintype "passive"))
      (node (ref "SJ6") (pin "1") (pinfunction "1_1") (pintype "passive"))
      (node (ref "SJ7") (pin "1") (pinfunction "1_1") (pintype "passive"))
      (node (ref "SJ8") (pin "1") (pinfunction "1_1") (pintype "passive"))
      (node (ref "SJ9") (pin "1") (pinfunction "1_1") (pintype "passive"))
      (node (ref "TFT") (pin "3") (pinfunction "3_3") (pintype "passive"))
      (node (ref "TX_LED") (pin "A") (pinfunction "A_A") (pintype "passive"))
      (node (ref "U$1") (pin "VDD") (pinfunction "VDD_VDD") (pintype "power_in"))
      (node (ref "U$6") (pin "VDD") (pinfunction "VDD_VDD") (pintype "power_in"))
      (node (ref "U$7") (pin "VDD") (pinfunction "VDD_VDD") (pintype "power_in"))
      (node (ref "U1") (pin "5V@0") (pinfunction "5V_5V@0") (pintype "power_in"))
      (node (ref "U1") (pin "5V@1") (pinfunction "5V_5V@1") (pintype "power_in"))
      (node (ref "U1") (pin "5V@2") (pinfunction "5V_5V@2") (pintype "power_in"))
    )
    (net (code "126") (name "unconnected-(TFT-Pad2)") (class "Default")
      (node (ref "TFT") (pin "2") (pinfunction "2_2") (pintype "passive"))
    )
    (net (code "127") (name "unconnected-(TFT-Pad4)") (class "Default")
      (node (ref "TFT") (pin "4") (pinfunction "4_4") (pintype "passive"))
    )
    (net (code "128") (name "unconnected-(TFT-Pad5)") (class "Default")
      (node (ref "TFT") (pin "5") (pinfunction "5_5") (pintype "passive"))
    )
    (net (code "129") (name "unconnected-(TFT-Pad6)") (class "Default")
      (node (ref "TFT") (pin "6") (pinfunction "6_6") (pintype "passive"))
    )
    (net (code "130") (name "unconnected-(TFT-Pad8)") (class "Default")
      (node (ref "TFT") (pin "8") (pinfunction "8_8") (pintype "passive"))
    )
    (net (code "131") (name "unconnected-(TFT-Pad10)") (class "Default")
      (node (ref "TFT") (pin "10") (pinfunction "10_10") (pintype "passive"))
    )
    (net (code "132") (name "unconnected-(TFT-Pad12)") (class "Default")
      (node (ref "TFT") (pin "12") (pinfunction "12_12") (pintype "passive"))
    )
    (net (code "133") (name "unconnected-(TFT-Pad14)") (class "Default")
      (node (ref "TFT") (pin "14") (pinfunction "14_14") (pintype "passive"))
    )
    (net (code "134") (name "unconnected-(TFT-Pad16)") (class "Default")
      (node (ref "TFT") (pin "16") (pinfunction "16_16") (pintype "passive"))
    )
    (net (code "135") (name "unconnected-(TFT-Pad24)") (class "Default")
      (node (ref "TFT") (pin "24") (pinfunction "24_24") (pintype "passive"))
    )
    (net (code "136") (name "unconnected-(TFT-Pad31)") (class "Default")
      (node (ref "TFT") (pin "31") (pinfunction "31_31") (pintype "passive"))
    )
    (net (code "137") (name "unconnected-(TFT-Pad35)") (class "Default")
      (node (ref "TFT") (pin "35") (pinfunction "35_35") (pintype "passive"))
    )
    (net (code "138") (name "unconnected-(TFT-Pad38)") (class "Default")
      (node (ref "TFT") (pin "38") (pinfunction "38_38") (pintype "passive"))
    )
    (net (code "139") (name "unconnected-(TFT-Pad39)") (class "Default")
      (node (ref "TFT") (pin "39") (pinfunction "39_39") (pintype "passive"))
    )
    (net (code "140") (name "unconnected-(TFT-Pad40)") (class "Default")
      (node (ref "TFT") (pin "40") (pinfunction "40_40") (pintype "passive"))
    )
  )
)
